# Lichtsteuerung.net
KiCad netlist of a schematic drawn in EAGLE
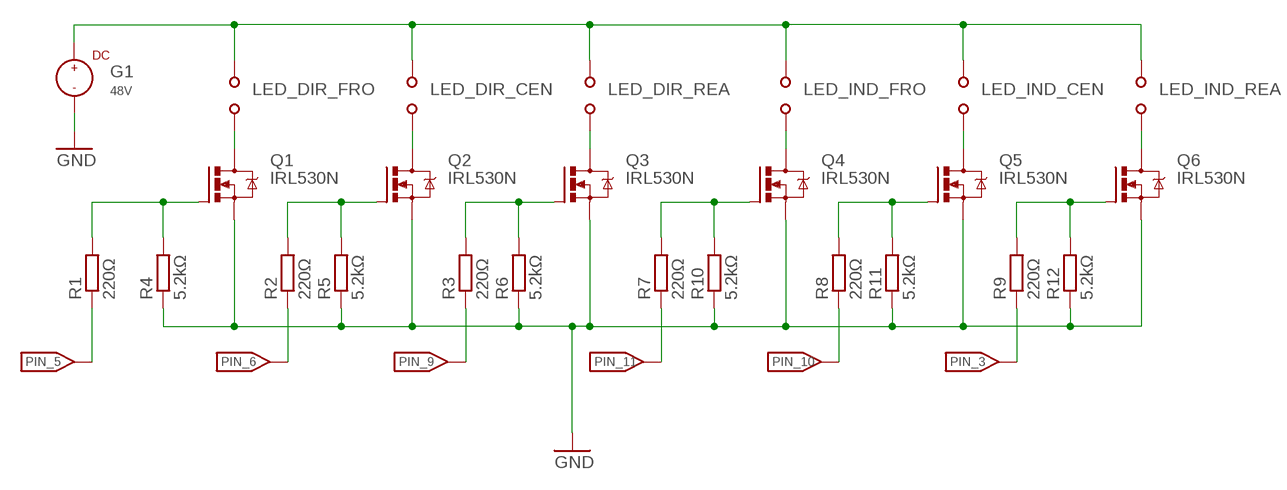
[diagram p0: schematic, sheet 1]

(export (version "E")
  (design (tool "Eeschema 10.0.6"))
  (components
    (comp (ref "G1")
      (value "48V")
      (footprint "eagle-import:TEMP_2")
      (libsource (lib "eagle-import") (part "DC-POWER"))
    )
    (comp (ref "Q1")
      (value "IRL530N")
      (footprint "eagle-import:TO220BV")
      (libsource (lib "eagle-import") (part "IRL530N"))
    )
    (comp (ref "Q2")
      (value "IRL530N")
      (footprint "eagle-import:TO220BV")
      (libsource (lib "eagle-import") (part "IRL530N"))
    )
    (comp (ref "Q3")
      (value "IRL530N")
      (footprint "eagle-import:TO220BV")
      (libsource (lib "eagle-import") (part "IRL530N"))
    )
    (comp (ref "Q4")
      (value "IRL530N")
      (footprint "eagle-import:TO220BV")
      (libsource (lib "eagle-import") (part "IRL530N"))
    )
    (comp (ref "Q5")
      (value "IRL530N")
      (footprint "eagle-import:TO220BV")
      (libsource (lib "eagle-import") (part "IRL530N"))
    )
    (comp (ref "Q6")
      (value "IRL530N")
      (footprint "eagle-import:TO220BV")
      (libsource (lib "eagle-import") (part "IRL530N"))
    )
    (comp (ref "R1")
      (value "220Ω")
      (footprint "eagle-import:0204V")
      (libsource (lib "eagle-import") (part "R-EU_0204/2V"))
    )
    (comp (ref "R2")
      (value "220Ω")
      (footprint "eagle-import:0204V")
      (libsource (lib "eagle-import") (part "R-EU_0204/2V"))
    )
    (comp (ref "R3")
      (value "220Ω")
      (footprint "eagle-import:0204V")
      (libsource (lib "eagle-import") (part "R-EU_0204/2V"))
    )
    (comp (ref "R4")
      (value "5.2kΩ")
      (footprint "eagle-import:0204V")
      (libsource (lib "eagle-import") (part "R-EU_0204/2V"))
    )
    (comp (ref "R5")
      (value "5.2kΩ")
      (footprint "eagle-import:0204V")
      (libsource (lib "eagle-import") (part "R-EU_0204/2V"))
    )
    (comp (ref "R6")
      (value "5.2kΩ")
      (footprint "eagle-import:0204V")
      (libsource (lib "eagle-import") (part "R-EU_0204/2V"))
    )
    (comp (ref "R7")
      (value "220Ω")
      (footprint "eagle-import:0204V")
      (libsource (lib "eagle-import") (part "R-EU_0204/2V"))
    )
    (comp (ref "R8")
      (value "220Ω")
      (footprint "eagle-import:0204V")
      (libsource (lib "eagle-import") (part "R-EU_0204/2V"))
    )
    (comp (ref "R9")
      (value "220Ω")
      (footprint "eagle-import:0204V")
      (libsource (lib "eagle-import") (part "R-EU_0204/2V"))
    )
    (comp (ref "R10")
      (value "5.2kΩ")
      (footprint "eagle-import:0204V")
      (libsource (lib "eagle-import") (part "R-EU_0204/2V"))
    )
    (comp (ref "R11")
      (value "5.2kΩ")
      (footprint "eagle-import:0204V")
      (libsource (lib "eagle-import") (part "R-EU_0204/2V"))
    )
    (comp (ref "R12")
      (value "5.2kΩ")
      (footprint "eagle-import:0204V")
      (libsource (lib "eagle-import") (part "R-EU_0204/2V"))
    )
  )
  (nets
    (net (code "1") (name "Net-(Q1-PadG)") (class "Default")
      (node (ref "Q1") (pin "G") (pinfunction "G_G") (pintype "passive"))
      (node (ref "R1") (pin "2") (pinfunction "2_2") (pintype "passive"))
      (node (ref "R4") (pin "2") (pinfunction "2_2") (pintype "passive"))
    )
    (net (code "2") (name "Net-(Q1-PadS)") (class "Default")
      (node (ref "Q1") (pin "S") (pinfunction "S_S") (pintype "passive"))
      (node (ref "Q2") (pin "S") (pinfunction "S_S") (pintype "passive"))
      (node (ref "Q3") (pin "S") (pinfunction "S_S") (pintype "passive"))
      (node (ref "Q4") (pin "S") (pinfunction "S_S") (pintype "passive"))
      (node (ref "Q5") (pin "S") (pinfunction "S_S") (pintype "passive"))
      (node (ref "Q6") (pin "S") (pinfunction "S_S") (pintype "passive"))
      (node (ref "R10") (pin "1") (pinfunction "1_1") (pintype "passive"))
      (node (ref "R11") (pin "1") (pinfunction "1_1") (pintype "passive"))
      (node (ref "R12") (pin "1") (pinfunction "1_1") (pintype "passive"))
      (node (ref "R4") (pin "1") (pinfunction "1_1") (pintype "passive"))
      (node (ref "R5") (pin "1") (pinfunction "1_1") (pintype "passive"))
      (node (ref "R6") (pin "1") (pinfunction "1_1") (pintype "passive"))
    )
    (net (code "3") (name "Net-(Q2-PadG)") (class "Default")
      (node (ref "Q2") (pin "G") (pinfunction "G_G") (pintype "passive"))
      (node (ref "R2") (pin "2") (pinfunction "2_2") (pintype "passive"))
      (node (ref "R5") (pin "2") (pinfunction "2_2") (pintype "passive"))
    )
    (net (code "4") (name "Net-(Q3-PadG)") (class "Default")
      (node (ref "Q3") (pin "G") (pinfunction "G_G") (pintype "passive"))
      (node (ref "R3") (pin "2") (pinfunction "2_2") (pintype "passive"))
      (node (ref "R6") (pin "2") (pinfunction "2_2") (pintype "passive"))
    )
    (net (code "5") (name "Net-(Q4-PadG)") (class "Default")
      (node (ref "Q4") (pin "G") (pinfunction "G_G") (pintype "passive"))
      (node (ref "R10") (pin "2") (pinfunction "2_2") (pintype "passive"))
      (node (ref "R7") (pin "2") (pinfunction "2_2") (pintype "passive"))
    )
    (net (code "6") (name "Net-(Q5-PadG)") (class "Default")
      (node (ref "Q5") (pin "G") (pinfunction "G_G") (pintype "passive"))
      (node (ref "R11") (pin "2") (pinfunction "2_2") (pintype "passive"))
      (node (ref "R8") (pin "2") (pinfunction "2_2") (pintype "passive"))
    )
    (net (code "7") (name "Net-(Q6-PadG)") (class "Default")
      (node (ref "Q6") (pin "G") (pinfunction "G_G") (pintype "passive"))
      (node (ref "R12") (pin "2") (pinfunction "2_2") (pintype "passive"))
      (node (ref "R9") (pin "2") (pinfunction "2_2") (pintype "passive"))
    )
    (net (code "8") (name "unconnected-(Q1-PadD)") (class "Default")
      (node (ref "Q1") (pin "D") (pinfunction "D_D") (pintype "passive"))
    )
    (net (code "9") (name "unconnected-(Q2-PadD)") (class "Default")
      (node (ref "Q2") (pin "D") (pinfunction "D_D") (pintype "passive"))
    )
    (net (code "10") (name "unconnected-(Q3-PadD)") (class "Default")
      (node (ref "Q3") (pin "D") (pinfunction "D_D") (pintype "passive"))
    )
    (net (code "11") (name "unconnected-(Q4-PadD)") (class "Default")
      (node (ref "Q4") (pin "D") (pinfunction "D_D") (pintype "passive"))
    )
    (net (code "12") (name "unconnected-(Q5-PadD)") (class "Default")
      (node (ref "Q5") (pin "D") (pinfunction "D_D") (pintype "passive"))
    )
    (net (code "13") (name "unconnected-(Q6-PadD)") (class "Default")
      (node (ref "Q6") (pin "D") (pinfunction "D_D") (pintype "passive"))
    )
    (net (code "14") (name "unconnected-(R1-Pad1)") (class "Default")
      (node (ref "R1") (pin "1") (pinfunction "1_1") (pintype "passive"))
    )
    (net (code "15") (name "unconnected-(R2-Pad1)") (class "Default")
      (node (ref "R2") (pin "1") (pinfunction "1_1") (pintype "passive"))
    )
    (net (code "16") (name "unconnected-(R3-Pad1)") (class "Default")
      (node (ref "R3") (pin "1") (pinfunction "1_1") (pintype "passive"))
    )
    (net (code "17") (name "unconnected-(R7-Pad1)") (class "Default")
      (node (ref "R7") (pin "1") (pinfunction "1_1") (pintype "passive"))
    )
    (net (code "18") (name "unconnected-(R8-Pad1)") (class "Default")
      (node (ref "R8") (pin "1") (pinfunction "1_1") (pintype "passive"))
    )
    (net (code "19") (name "unconnected-(R9-Pad1)") (class "Default")
      (node (ref "R9") (pin "1") (pinfunction "1_1") (pintype "passive"))
    )
  )
)
